# RasPi_Hat_Temp.net
KiCad netlist of a schematic drawn in Altium Designer
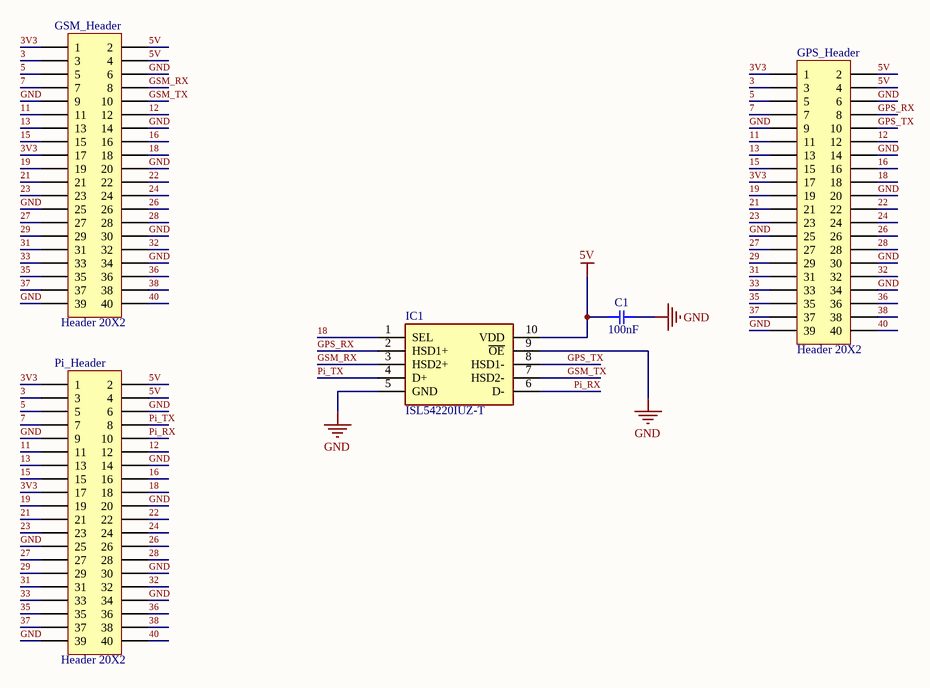
[diagram p0: RasPi_Hat_Temp.SchDoc]

(export (version "E")
  (design (tool "Eeschema 10.0.6"))
  (components
    (comp (ref "C1")
      (value "100nF")
      (footprint "SMD-0402C")
      (description "CAP CER 1UF 10V X7S 0402")
      (fields
        (field (name "DIGI-KEY PART NUMBER") "490-13409-1-ND")
        (field (name "PART NUMBER") "GCM155C71A105KE38D")
      )
      (libsource (lib "capacitor_murata_0402") (part "GCM155C71A105KE38D"))
    )
    (comp (ref "GPS_Header")
      (value "Header 20X2")
      (footprint "HDR2X20")
      (description "Header, 20-Pin, Dual row")
      (fields (field (name "PUBLISHER") "Altium Limited"))
      (libsource (lib "Miscellaneous Connectors") (part "Header 20X2"))
    )
    (comp (ref "GSM_Header")
      (value "Header 20X2")
      (footprint "HDR2X20")
      (description "Header, 20-Pin, Dual row")
      (fields (field (name "PUBLISHER") "Altium Limited"))
      (libsource (lib "Miscellaneous Connectors") (part "Header 20X2"))
    )
    (comp (ref "IC1")
      (value "ISL54220IUZ-T")
      (footprint "SamacSys:SOP50P490X110-10N")
      (description "Integrated Circuit")
      (fields (field (name "MOUSER PART NUMBER") "968-ISL54220IUZ-T"))
      (libsource (lib "*") (part "ISL54220IUZ-T"))
    )
    (comp (ref "Pi_Header")
      (value "Header 20X2")
      (footprint "HDR2X20")
      (description "Header, 20-Pin, Dual row")
      (fields (field (name "PUBLISHER") "Altium Limited"))
      (libsource (lib "Miscellaneous Connectors") (part "Header 20X2"))
    )
  )
  (nets
    (net (code "1") (name "/3") (class "Default")
      (node (ref "GPS_Header") (pin "3") (pinfunction "3_3") (pintype "passive"))
      (node (ref "GSM_Header") (pin "3") (pinfunction "3_3") (pintype "passive"))
      (node (ref "Pi_Header") (pin "3") (pinfunction "3_3") (pintype "passive"))
    )
    (net (code "2") (name "/3V3") (class "Default")
      (node (ref "GPS_Header") (pin "1") (pinfunction "1_1") (pintype "passive"))
      (node (ref "GPS_Header") (pin "17") (pinfunction "17_17") (pintype "passive"))
      (node (ref "GSM_Header") (pin "1") (pinfunction "1_1") (pintype "passive"))
      (node (ref "GSM_Header") (pin "17") (pinfunction "17_17") (pintype "passive"))
      (node (ref "Pi_Header") (pin "1") (pinfunction "1_1") (pintype "passive"))
      (node (ref "Pi_Header") (pin "17") (pinfunction "17_17") (pintype "passive"))
    )
    (net (code "3") (name "/5") (class "Default")
      (node (ref "GPS_Header") (pin "5") (pinfunction "5_5") (pintype "passive"))
      (node (ref "GSM_Header") (pin "5") (pinfunction "5_5") (pintype "passive"))
      (node (ref "Pi_Header") (pin "5") (pinfunction "5_5") (pintype "passive"))
    )
    (net (code "4") (name "/7") (class "Default")
      (node (ref "GPS_Header") (pin "7") (pinfunction "7_7") (pintype "passive"))
      (node (ref "GSM_Header") (pin "7") (pinfunction "7_7") (pintype "passive"))
      (node (ref "Pi_Header") (pin "7") (pinfunction "7_7") (pintype "passive"))
    )
    (net (code "5") (name "/11") (class "Default")
      (node (ref "GPS_Header") (pin "11") (pinfunction "11_11") (pintype "passive"))
      (node (ref "GSM_Header") (pin "11") (pinfunction "11_11") (pintype "passive"))
      (node (ref "Pi_Header") (pin "11") (pinfunction "11_11") (pintype "passive"))
    )
    (net (code "6") (name "/12") (class "Default")
      (node (ref "GPS_Header") (pin "12") (pinfunction "12_12") (pintype "passive"))
      (node (ref "GSM_Header") (pin "12") (pinfunction "12_12") (pintype "passive"))
      (node (ref "Pi_Header") (pin "12") (pinfunction "12_12") (pintype "passive"))
    )
    (net (code "7") (name "/13") (class "Default")
      (node (ref "GPS_Header") (pin "13") (pinfunction "13_13") (pintype "passive"))
      (node (ref "GSM_Header") (pin "13") (pinfunction "13_13") (pintype "passive"))
      (node (ref "Pi_Header") (pin "13") (pinfunction "13_13") (pintype "passive"))
    )
    (net (code "8") (name "/15") (class "Default")
      (node (ref "GPS_Header") (pin "15") (pinfunction "15_15") (pintype "passive"))
      (node (ref "GSM_Header") (pin "15") (pinfunction "15_15") (pintype "passive"))
      (node (ref "Pi_Header") (pin "15") (pinfunction "15_15") (pintype "passive"))
    )
    (net (code "9") (name "/16") (class "Default")
      (node (ref "GPS_Header") (pin "16") (pinfunction "16_16") (pintype "passive"))
      (node (ref "GSM_Header") (pin "16") (pinfunction "16_16") (pintype "passive"))
      (node (ref "Pi_Header") (pin "16") (pinfunction "16_16") (pintype "passive"))
    )
    (net (code "10") (name "/18") (class "Default")
      (node (ref "GPS_Header") (pin "18") (pinfunction "18_18") (pintype "passive"))
      (node (ref "GSM_Header") (pin "18") (pinfunction "18_18") (pintype "passive"))
      (node (ref "IC1") (pin "1") (pinfunction "SEL_1") (pintype "passive"))
      (node (ref "Pi_Header") (pin "18") (pinfunction "18_18") (pintype "passive"))
    )
    (net (code "11") (name "/19") (class "Default")
      (node (ref "GPS_Header") (pin "19") (pinfunction "19_19") (pintype "passive"))
      (node (ref "GSM_Header") (pin "19") (pinfunction "19_19") (pintype "passive"))
      (node (ref "Pi_Header") (pin "19") (pinfunction "19_19") (pintype "passive"))
    )
    (net (code "12") (name "/21") (class "Default")
      (node (ref "GPS_Header") (pin "21") (pinfunction "21_21") (pintype "passive"))
      (node (ref "GSM_Header") (pin "21") (pinfunction "21_21") (pintype "passive"))
      (node (ref "Pi_Header") (pin "21") (pinfunction "21_21") (pintype "passive"))
    )
    (net (code "13") (name "/22") (class "Default")
      (node (ref "GPS_Header") (pin "22") (pinfunction "22_22") (pintype "passive"))
      (node (ref "GSM_Header") (pin "22") (pinfunction "22_22") (pintype "passive"))
      (node (ref "Pi_Header") (pin "22") (pinfunction "22_22") (pintype "passive"))
    )
    (net (code "14") (name "/23") (class "Default")
      (node (ref "GPS_Header") (pin "23") (pinfunction "23_23") (pintype "passive"))
      (node (ref "GSM_Header") (pin "23") (pinfunction "23_23") (pintype "passive"))
      (node (ref "Pi_Header") (pin "23") (pinfunction "23_23") (pintype "passive"))
    )
    (net (code "15") (name "/24") (class "Default")
      (node (ref "GPS_Header") (pin "24") (pinfunction "24_24") (pintype "passive"))
      (node (ref "GSM_Header") (pin "24") (pinfunction "24_24") (pintype "passive"))
      (node (ref "Pi_Header") (pin "24") (pinfunction "24_24") (pintype "passive"))
    )
    (net (code "16") (name "/26") (class "Default")
      (node (ref "GPS_Header") (pin "26") (pinfunction "26_26") (pintype "passive"))
      (node (ref "GSM_Header") (pin "26") (pinfunction "26_26") (pintype "passive"))
      (node (ref "Pi_Header") (pin "26") (pinfunction "26_26") (pintype "passive"))
    )
    (net (code "17") (name "/27") (class "Default")
      (node (ref "GPS_Header") (pin "27") (pinfunction "27_27") (pintype "passive"))
      (node (ref "GSM_Header") (pin "27") (pinfunction "27_27") (pintype "passive"))
      (node (ref "Pi_Header") (pin "27") (pinfunction "27_27") (pintype "passive"))
    )
    (net (code "18") (name "/28") (class "Default")
      (node (ref "GPS_Header") (pin "28") (pinfunction "28_28") (pintype "passive"))
      (node (ref "GSM_Header") (pin "28") (pinfunction "28_28") (pintype "passive"))
      (node (ref "Pi_Header") (pin "28") (pinfunction "28_28") (pintype "passive"))
    )
    (net (code "19") (name "/29") (class "Default")
      (node (ref "GPS_Header") (pin "29") (pinfunction "29_29") (pintype "passive"))
      (node (ref "GSM_Header") (pin "29") (pinfunction "29_29") (pintype "passive"))
      (node (ref "Pi_Header") (pin "29") (pinfunction "29_29") (pintype "passive"))
    )
    (net (code "20") (name "/31") (class "Default")
      (node (ref "GPS_Header") (pin "31") (pinfunction "31_31") (pintype "passive"))
      (node (ref "GSM_Header") (pin "31") (pinfunction "31_31") (pintype "passive"))
      (node (ref "Pi_Header") (pin "31") (pinfunction "31_31") (pintype "passive"))
    )
    (net (code "21") (name "/32") (class "Default")
      (node (ref "GPS_Header") (pin "32") (pinfunction "32_32") (pintype "passive"))
      (node (ref "GSM_Header") (pin "32") (pinfunction "32_32") (pintype "passive"))
      (node (ref "Pi_Header") (pin "32") (pinfunction "32_32") (pintype "passive"))
    )
    (net (code "22") (name "/33") (class "Default")
      (node (ref "GPS_Header") (pin "33") (pinfunction "33_33") (pintype "passive"))
      (node (ref "GSM_Header") (pin "33") (pinfunction "33_33") (pintype "passive"))
      (node (ref "Pi_Header") (pin "33") (pinfunction "33_33") (pintype "passive"))
    )
    (net (code "23") (name "/35") (class "Default")
      (node (ref "GPS_Header") (pin "35") (pinfunction "35_35") (pintype "passive"))
      (node (ref "GSM_Header") (pin "35") (pinfunction "35_35") (pintype "passive"))
      (node (ref "Pi_Header") (pin "35") (pinfunction "35_35") (pintype "passive"))
    )
    (net (code "24") (name "/36") (class "Default")
      (node (ref "GPS_Header") (pin "36") (pinfunction "36_36") (pintype "passive"))
      (node (ref "GSM_Header") (pin "36") (pinfunction "36_36") (pintype "passive"))
      (node (ref "Pi_Header") (pin "36") (pinfunction "36_36") (pintype "passive"))
    )
    (net (code "25") (name "/37") (class "Default")
      (node (ref "GPS_Header") (pin "37") (pinfunction "37_37") (pintype "passive"))
      (node (ref "GSM_Header") (pin "37") (pinfunction "37_37") (pintype "passive"))
      (node (ref "Pi_Header") (pin "37") (pinfunction "37_37") (pintype "passive"))
    )
    (net (code "26") (name "/38") (class "Default")
      (node (ref "GPS_Header") (pin "38") (pinfunction "38_38") (pintype "passive"))
      (node (ref "GSM_Header") (pin "38") (pinfunction "38_38") (pintype "passive"))
      (node (ref "Pi_Header") (pin "38") (pinfunction "38_38") (pintype "passive"))
    )
    (net (code "27") (name "/40") (class "Default")
      (node (ref "GPS_Header") (pin "40") (pinfunction "40_40") (pintype "passive"))
      (node (ref "GSM_Header") (pin "40") (pinfunction "40_40") (pintype "passive"))
      (node (ref "Pi_Header") (pin "40") (pinfunction "40_40") (pintype "passive"))
    )
    (net (code "28") (name "/GPS_RX") (class "Default")
      (node (ref "GPS_Header") (pin "8") (pinfunction "8_8") (pintype "passive"))
      (node (ref "IC1") (pin "2") (pinfunction "HSD1+_2") (pintype "passive"))
    )
    (net (code "29") (name "/GPS_TX") (class "Default")
      (node (ref "GPS_Header") (pin "10") (pinfunction "10_10") (pintype "passive"))
      (node (ref "IC1") (pin "8") (pinfunction "HSD1-_8") (pintype "passive"))
    )
    (net (code "30") (name "/GSM_RX") (class "Default")
      (node (ref "GSM_Header") (pin "8") (pinfunction "8_8") (pintype "passive"))
      (node (ref "IC1") (pin "3") (pinfunction "HSD2+_3") (pintype "passive"))
    )
    (net (code "31") (name "/GSM_TX") (class "Default")
      (node (ref "GSM_Header") (pin "10") (pinfunction "10_10") (pintype "passive"))
      (node (ref "IC1") (pin "7") (pinfunction "HSD2-_7") (pintype "passive"))
    )
    (net (code "32") (name "/Pi_RX") (class "Default")
      (node (ref "IC1") (pin "6") (pinfunction "D-_6") (pintype "passive"))
      (node (ref "Pi_Header") (pin "10") (pinfunction "10_10") (pintype "passive"))
    )
    (net (code "33") (name "/Pi_TX") (class "Default")
      (node (ref "IC1") (pin "4") (pinfunction "D+_4") (pintype "passive"))
      (node (ref "Pi_Header") (pin "8") (pinfunction "8_8") (pintype "passive"))
    )
    (net (code "34") (name "5V") (class "Default")
      (node (ref "C1") (pin "1") (pinfunction "1_1") (pintype "passive"))
      (node (ref "GPS_Header") (pin "2") (pinfunction "2_2") (pintype "passive"))
      (node (ref "GPS_Header") (pin "4") (pinfunction "4_4") (pintype "passive"))
      (node (ref "GSM_Header") (pin "2") (pinfunction "2_2") (pintype "passive"))
      (node (ref "GSM_Header") (pin "4") (pinfunction "4_4") (pintype "passive"))
      (node (ref "IC1") (pin "10") (pinfunction "VDD_10") (pintype "passive"))
      (node (ref "Pi_Header") (pin "2") (pinfunction "2_2") (pintype "passive"))
      (node (ref "Pi_Header") (pin "4") (pinfunction "4_4") (pintype "passive"))
    )
    (net (code "35") (name "GND") (class "Default")
      (node (ref "C1") (pin "2") (pinfunction "2_2") (pintype "passive"))
      (node (ref "GPS_Header") (pin "14") (pinfunction "14_14") (pintype "passive"))
      (node (ref "GPS_Header") (pin "20") (pinfunction "20_20") (pintype "passive"))
      (node (ref "GPS_Header") (pin "25") (pinfunction "25_25") (pintype "passive"))
      (node (ref "GPS_Header") (pin "30") (pinfunction "30_30") (pintype "passive"))
      (node (ref "GPS_Header") (pin "34") (pinfunction "34_34") (pintype "passive"))
      (node (ref "GPS_Header") (pin "39") (pinfunction "39_39") (pintype "passive"))
      (node (ref "GPS_Header") (pin "6") (pinfunction "6_6") (pintype "passive"))
      (node (ref "GPS_Header") (pin "9") (pinfunction "9_9") (pintype "passive"))
      (node (ref "GSM_Header") (pin "14") (pinfunction "14_14") (pintype "passive"))
      (node (ref "GSM_Header") (pin "20") (pinfunction "20_20") (pintype "passive"))
      (node (ref "GSM_Header") (pin "25") (pinfunction "25_25") (pintype "passive"))
      (node (ref "GSM_Header") (pin "30") (pinfunction "30_30") (pintype "passive"))
      (node (ref "GSM_Header") (pin "34") (pinfunction "34_34") (pintype "passive"))
      (node (ref "GSM_Header") (pin "39") (pinfunction "39_39") (pintype "passive"))
      (node (ref "GSM_Header") (pin "6") (pinfunction "6_6") (pintype "passive"))
      (node (ref "GSM_Header") (pin "9") (pinfunction "9_9") (pintype "passive"))
      (node (ref "IC1") (pin "5") (pinfunction "GND_5") (pintype "passive"))
      (node (ref "IC1") (pin "9") (pinfunction "~{OE}_9") (pintype "passive"))
      (node (ref "Pi_Header") (pin "14") (pinfunction "14_14") (pintype "passive"))
      (node (ref "Pi_Header") (pin "20") (pinfunction "20_20") (pintype "passive"))
      (node (ref "Pi_Header") (pin "25") (pinfunction "25_25") (pintype "passive"))
      (node (ref "Pi_Header") (pin "30") (pinfunction "30_30") (pintype "passive"))
      (node (ref "Pi_Header") (pin "34") (pinfunction "34_34") (pintype "passive"))
      (node (ref "Pi_Header") (pin "39") (pinfunction "39_39") (pintype "passive"))
      (node (ref "Pi_Header") (pin "6") (pinfunction "6_6") (pintype "passive"))
      (node (ref "Pi_Header") (pin "9") (pinfunction "9_9") (pintype "passive"))
    )
  )
)
